# USB-C.net
KiCad netlist of a schematic drawn in Altium Designer
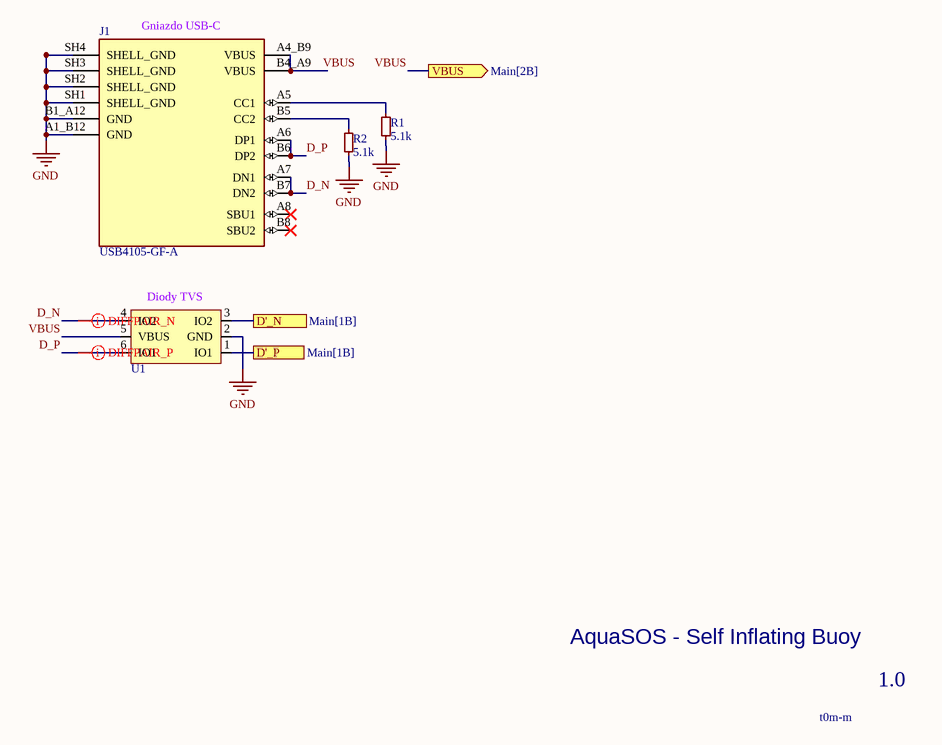
[diagram p0: USB-C.SchDoc]

(export (version "E")
  (design (tool "Eeschema 10.0.6"))
  (components
    (comp (ref "J1")
      (value "USB4105-GF-A")
      (footprint "GCT_USB4105-GF-A")
      (description "USB-C Connector, USB 2.0")
      (fields (field (name "MF") "{'manufacturer': u'GCT'}"))
      (libsource (lib "AquaSOS DevBoard") (part "USB4105-GF-A"))
    )
    (comp (ref "R1")
      (value "5.1k")
      (footprint "RC0402JR-075K1P")
      (description "5.1k resistor")
      (libsource (lib "AquaSOS DevBoard") (part "RC0402JR-075K1P"))
    )
    (comp (ref "R2")
      (value "5.1k")
      (footprint "RC0402JR-075K1P")
      (description "5.1k resistor")
      (libsource (lib "AquaSOS DevBoard") (part "RC0402JR-075K1P"))
    )
    (comp (ref "U1")
      (value "USBLC6-2SC6")
      (footprint "USBLC6-2SC6")
      (description "ESD/TVS Diodes")
      (libsource (lib "Schlib1") (part "USBLC6-2SC6"))
    )
  )
  (nets
    (net (code "1") (name "/D'_N") (class "Default")
      (node (ref "U1") (pin "3") (pinfunction "IO2_3") (pintype "passive"))
    )
    (net (code "2") (name "/D'_P") (class "Default")
      (node (ref "U1") (pin "1") (pinfunction "IO1_1") (pintype "passive"))
    )
    (net (code "3") (name "/D_N") (class "Default")
      (node (ref "J1") (pin "A7") (pinfunction "DN1_A7") (pintype "bidirectional"))
      (node (ref "J1") (pin "B7") (pinfunction "DN2_B7") (pintype "bidirectional"))
      (node (ref "U1") (pin "4") (pinfunction "IO2_4") (pintype "passive"))
    )
    (net (code "4") (name "/D_P") (class "Default")
      (node (ref "J1") (pin "A6") (pinfunction "DP1_A6") (pintype "bidirectional"))
      (node (ref "J1") (pin "B6") (pinfunction "DP2_B6") (pintype "bidirectional"))
      (node (ref "U1") (pin "6") (pinfunction "IO1_6") (pintype "passive"))
    )
    (net (code "5") (name "/VBUS") (class "Default")
      (node (ref "J1") (pin "A4_B9") (pinfunction "VBUS_A4_B9") (pintype "passive"))
      (node (ref "J1") (pin "B4_A9") (pinfunction "VBUS_B4_A9") (pintype "passive"))
      (node (ref "U1") (pin "5") (pinfunction "VBUS_5") (pintype "passive"))
    )
    (net (code "6") (name "GND") (class "Default")
      (node (ref "J1") (pin "A1_B12") (pinfunction "GND_A1_B12") (pintype "power_in"))
      (node (ref "J1") (pin "B1_A12") (pinfunction "GND_B1_A12") (pintype "power_in"))
      (node (ref "J1") (pin "SH1") (pinfunction "SHELL_GND_SH1") (pintype "power_in"))
      (node (ref "J1") (pin "SH2") (pinfunction "SHELL_GND_SH2") (pintype "power_in"))
      (node (ref "J1") (pin "SH3") (pinfunction "SHELL_GND_SH3") (pintype "power_in"))
      (node (ref "J1") (pin "SH4") (pinfunction "SHELL_GND_SH4") (pintype "power_in"))
      (node (ref "R1") (pin "2") (pinfunction "2_2") (pintype "passive"))
      (node (ref "R2") (pin "2") (pinfunction "2_2") (pintype "passive"))
      (node (ref "U1") (pin "2") (pinfunction "GND_2") (pintype "passive"))
    )
    (net (code "7") (name "Net-(J1-CC1)") (class "Default")
      (node (ref "J1") (pin "A5") (pinfunction "CC1_A5") (pintype "bidirectional"))
      (node (ref "R1") (pin "1") (pinfunction "1_1") (pintype "passive"))
    )
    (net (code "8") (name "Net-(J1-CC2)") (class "Default")
      (node (ref "J1") (pin "B5") (pinfunction "CC2_B5") (pintype "bidirectional"))
      (node (ref "R2") (pin "1") (pinfunction "1_1") (pintype "passive"))
    )
    (net (code "9") (name "unconnected-(J1-SBU1-PadA8)") (class "Default")
      (node (ref "J1") (pin "A8") (pinfunction "SBU1_A8") (pintype "bidirectional+no_connect"))
    )
    (net (code "10") (name "unconnected-(J1-SBU2-PadB8)") (class "Default")
      (node (ref "J1") (pin "B8") (pinfunction "SBU2_B8") (pintype "bidirectional+no_connect"))
    )
  )
)
